# 09-I225-2.net
KiCad netlist of a schematic drawn in Altium Designer
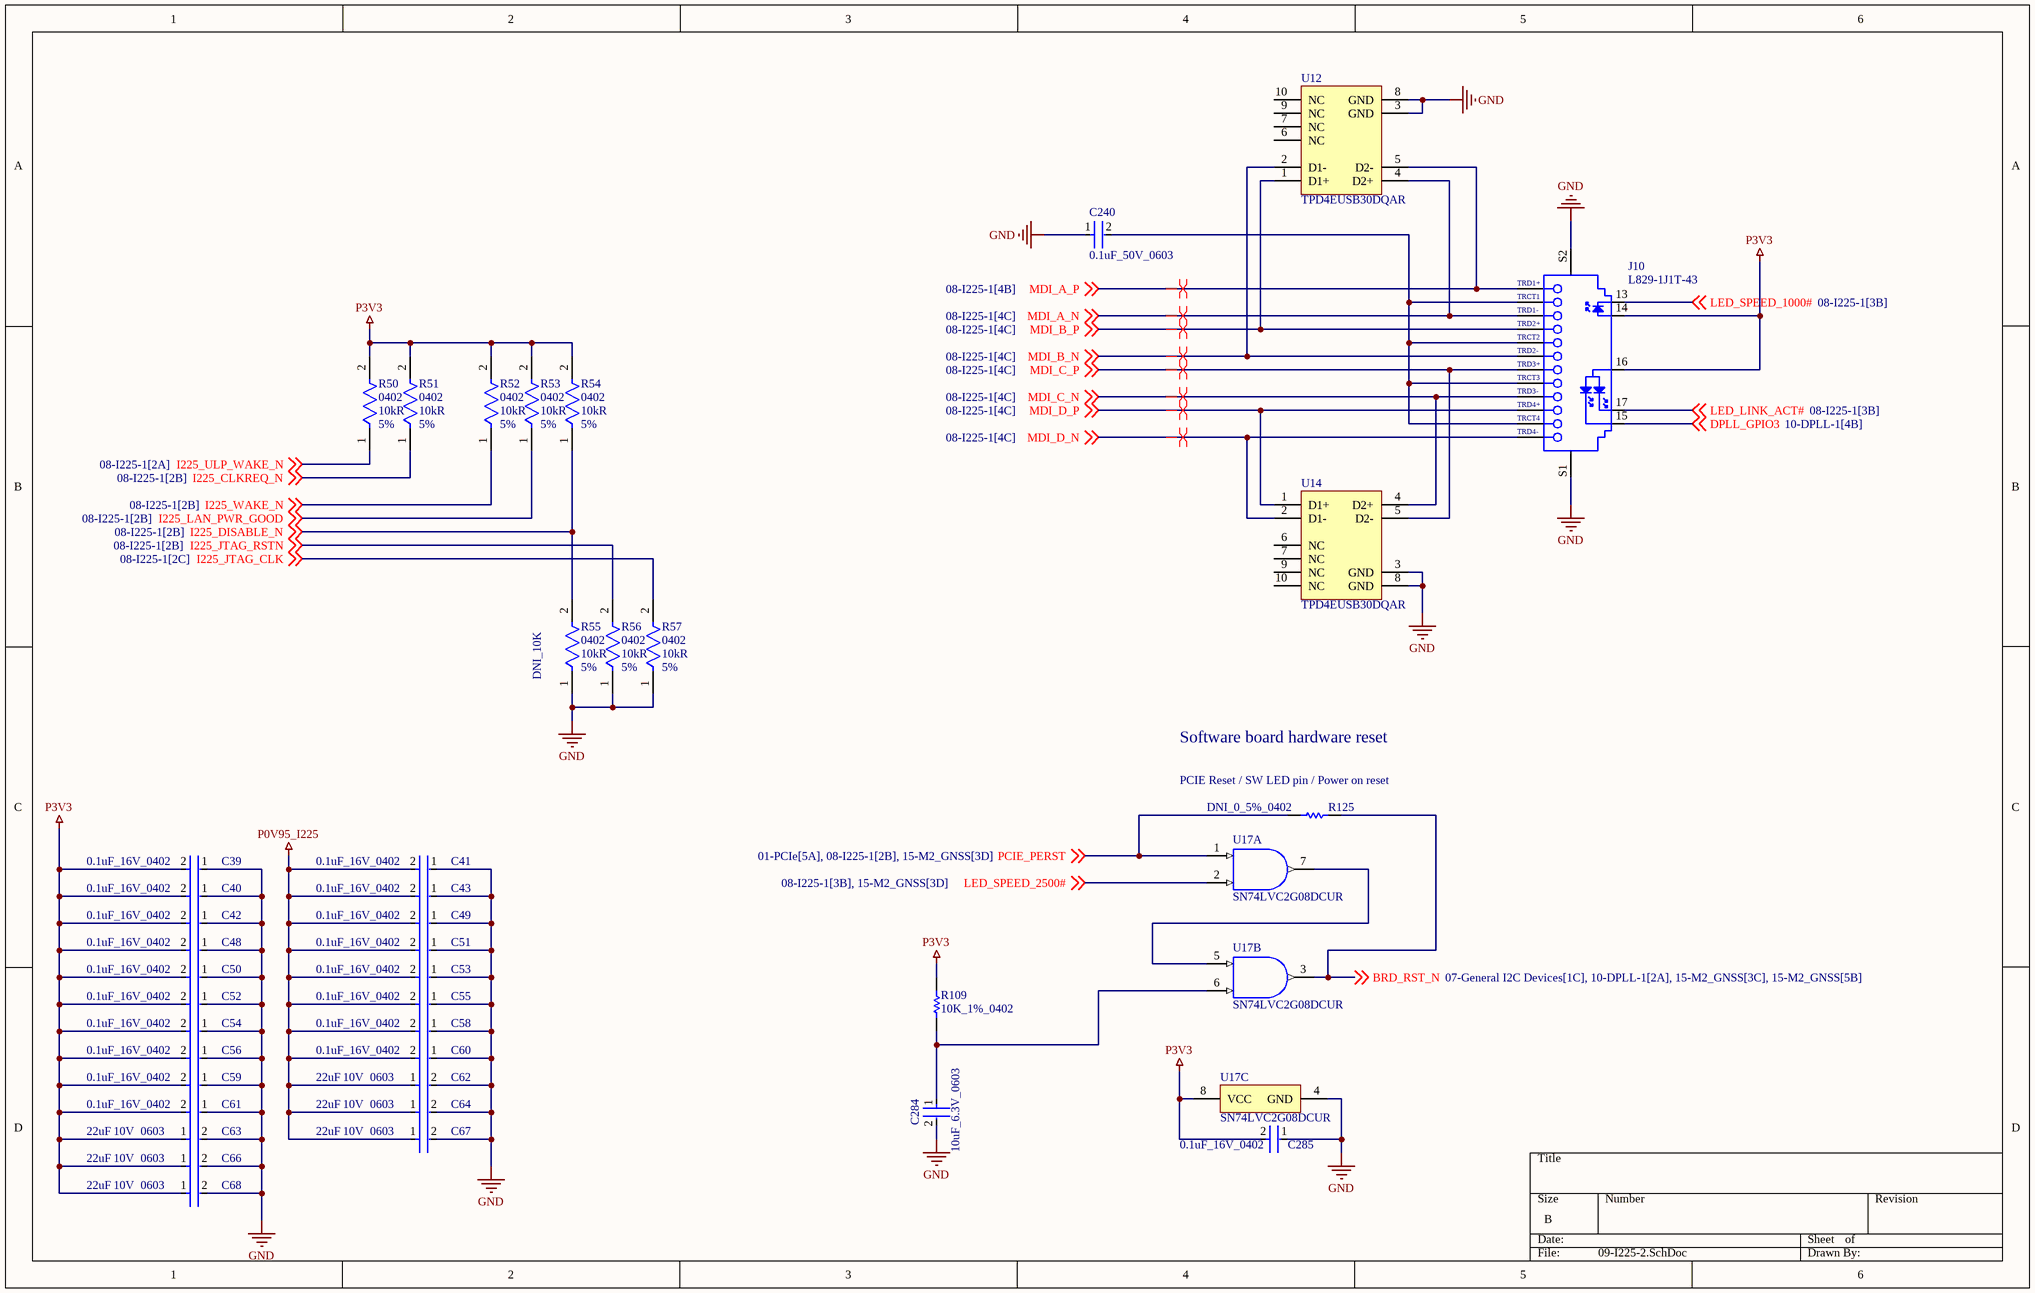
[diagram p0: 09-I225-2.SchDoc]

(export (version "E")
  (design (tool "Eeschema 10.0.6"))
  (components
    (comp (ref "C39")
      (value "0.1uF_16V_0402")
      (footprint "FP-GRM15-MFG")
      (description "CAP CER 0.1UF 16V X7R 0402")
      (fields (field (name "MANUFACTURER PART NUMBER") "GRM155R71C104KA88D") (field (name "TOLERANCE") "10%"))
      (libsource (lib "Altium Content Vault") (part "236180d848d6139a670b325ea6854c9"))
    )
    (comp (ref "C40")
      (value "0.1uF_16V_0402")
      (footprint "FP-GRM15-MFG")
      (description "CAP CER 0.1UF 16V X7R 0402")
      (fields (field (name "MANUFACTURER PART NUMBER") "GRM155R71C104KA88D") (field (name "TOLERANCE") "10%"))
      (libsource (lib "Altium Content Vault") (part "236180d848d6139a670b325ea6854c9"))
    )
    (comp (ref "C41")
      (value "0.1uF_16V_0402")
      (footprint "FP-GRM15-MFG")
      (description "CAP CER 0.1UF 16V X7R 0402")
      (fields (field (name "MANUFACTURER PART NUMBER") "GRM155R71C104KA88D") (field (name "TOLERANCE") "10%"))
      (libsource (lib "Altium Content Vault") (part "236180d848d6139a670b325ea6854c9"))
    )
    (comp (ref "C42")
      (value "0.1uF_16V_0402")
      (footprint "FP-GRM15-MFG")
      (description "CAP CER 0.1UF 16V X7R 0402")
      (fields (field (name "MANUFACTURER PART NUMBER") "GRM155R71C104KA88D") (field (name "TOLERANCE") "10%"))
      (libsource (lib "Altium Content Vault") (part "236180d848d6139a670b325ea6854c9"))
    )
    (comp (ref "C43")
      (value "0.1uF_16V_0402")
      (footprint "FP-GRM15-MFG")
      (description "CAP CER 0.1UF 16V X7R 0402")
      (fields (field (name "MANUFACTURER PART NUMBER") "GRM155R71C104KA88D") (field (name "TOLERANCE") "10%"))
      (libsource (lib "Altium Content Vault") (part "236180d848d6139a670b325ea6854c9"))
    )
    (comp (ref "C48")
      (value "0.1uF_16V_0402")
      (footprint "FP-GRM15-MFG")
      (description "CAP CER 0.1UF 16V X7R 0402")
      (fields (field (name "MANUFACTURER PART NUMBER") "GRM155R71C104KA88D") (field (name "TOLERANCE") "10%"))
      (libsource (lib "Altium Content Vault") (part "236180d848d6139a670b325ea6854c9"))
    )
    (comp (ref "C49")
      (value "0.1uF_16V_0402")
      (footprint "FP-GRM15-MFG")
      (description "CAP CER 0.1UF 16V X7R 0402")
      (fields (field (name "MANUFACTURER PART NUMBER") "GRM155R71C104KA88D") (field (name "TOLERANCE") "10%"))
      (libsource (lib "Altium Content Vault") (part "236180d848d6139a670b325ea6854c9"))
    )
    (comp (ref "C50")
      (value "0.1uF_16V_0402")
      (footprint "FP-GRM15-MFG")
      (description "CAP CER 0.1UF 16V X7R 0402")
      (fields (field (name "MANUFACTURER PART NUMBER") "GRM155R71C104KA88D") (field (name "TOLERANCE") "10%"))
      (libsource (lib "Altium Content Vault") (part "236180d848d6139a670b325ea6854c9"))
    )
    (comp (ref "C51")
      (value "0.1uF_16V_0402")
      (footprint "FP-GRM15-MFG")
      (description "CAP CER 0.1UF 16V X7R 0402")
      (fields (field (name "MANUFACTURER PART NUMBER") "GRM155R71C104KA88D") (field (name "TOLERANCE") "10%"))
      (libsource (lib "Altium Content Vault") (part "236180d848d6139a670b325ea6854c9"))
    )
    (comp (ref "C52")
      (value "0.1uF_16V_0402")
      (footprint "FP-GRM15-MFG")
      (description "CAP CER 0.1UF 16V X7R 0402")
      (fields (field (name "MANUFACTURER PART NUMBER") "GRM155R71C104KA88D") (field (name "TOLERANCE") "10%"))
      (libsource (lib "Altium Content Vault") (part "236180d848d6139a670b325ea6854c9"))
    )
    (comp (ref "C53")
      (value "0.1uF_16V_0402")
      (footprint "FP-GRM15-MFG")
      (description "CAP CER 0.1UF 16V X7R 0402")
      (fields (field (name "MANUFACTURER PART NUMBER") "GRM155R71C104KA88D") (field (name "TOLERANCE") "10%"))
      (libsource (lib "Altium Content Vault") (part "236180d848d6139a670b325ea6854c9"))
    )
    (comp (ref "C54")
      (value "0.1uF_16V_0402")
      (footprint "FP-GRM15-MFG")
      (description "CAP CER 0.1UF 16V X7R 0402")
      (fields (field (name "MANUFACTURER PART NUMBER") "GRM155R71C104KA88D") (field (name "TOLERANCE") "10%"))
      (libsource (lib "Altium Content Vault") (part "236180d848d6139a670b325ea6854c9"))
    )
    (comp (ref "C55")
      (value "0.1uF_16V_0402")
      (footprint "FP-GRM15-MFG")
      (description "CAP CER 0.1UF 16V X7R 0402")
      (fields (field (name "MANUFACTURER PART NUMBER") "GRM155R71C104KA88D") (field (name "TOLERANCE") "10%"))
      (libsource (lib "Altium Content Vault") (part "236180d848d6139a670b325ea6854c9"))
    )
    (comp (ref "C56")
      (value "0.1uF_16V_0402")
      (footprint "FP-GRM15-MFG")
      (description "CAP CER 0.1UF 16V X7R 0402")
      (fields (field (name "MANUFACTURER PART NUMBER") "GRM155R71C104KA88D") (field (name "TOLERANCE") "10%"))
      (libsource (lib "Altium Content Vault") (part "236180d848d6139a670b325ea6854c9"))
    )
    (comp (ref "C58")
      (value "0.1uF_16V_0402")
      (footprint "FP-GRM15-MFG")
      (description "CAP CER 0.1UF 16V X7R 0402")
      (fields (field (name "MANUFACTURER PART NUMBER") "GRM155R71C104KA88D") (field (name "TOLERANCE") "10%"))
      (libsource (lib "Altium Content Vault") (part "236180d848d6139a670b325ea6854c9"))
    )
    (comp (ref "C59")
      (value "0.1uF_16V_0402")
      (footprint "FP-GRM15-MFG")
      (description "CAP CER 0.1UF 16V X7R 0402")
      (fields (field (name "MANUFACTURER PART NUMBER") "GRM155R71C104KA88D") (field (name "TOLERANCE") "10%"))
      (libsource (lib "Altium Content Vault") (part "236180d848d6139a670b325ea6854c9"))
    )
    (comp (ref "C60")
      (value "0.1uF_16V_0402")
      (footprint "FP-GRM15-MFG")
      (description "CAP CER 0.1UF 16V X7R 0402")
      (fields (field (name "MANUFACTURER PART NUMBER") "GRM155R71C104KA88D") (field (name "TOLERANCE") "10%"))
      (libsource (lib "Altium Content Vault") (part "236180d848d6139a670b325ea6854c9"))
    )
    (comp (ref "C61")
      (value "0.1uF_16V_0402")
      (footprint "FP-GRM15-MFG")
      (description "CAP CER 0.1UF 16V X7R 0402")
      (fields (field (name "MANUFACTURER PART NUMBER") "GRM155R71C104KA88D") (field (name "TOLERANCE") "10%"))
      (libsource (lib "Altium Content Vault") (part "236180d848d6139a670b325ea6854c9"))
    )
    (comp (ref "C62")
      (value "GRM188R61A226ME15D")
      (footprint "FP-GRM188-0_2-IPC_C")
      (description "Chip Multilayer Ceramic Capacitors for General Purpose, 0603, 22uF, X5R, 15%, 20%, 10V")
      (fields
        (field (name "TOLERANCE") "20%")
        (field (name "CAPACITANCE") "22uF")
        (field (name "VOLTAGE RATING") "10V")
        (field (name "CASE CODE (IMPERIAL)") "0603")
      )
      (libsource (lib "Altium Content Vault") (part "11868f565c42a9108669ba33697ecf6"))
    )
    (comp (ref "C63")
      (value "GRM188R61A226ME15D")
      (footprint "FP-GRM188-0_2-IPC_C")
      (description "Chip Multilayer Ceramic Capacitors for General Purpose, 0603, 22uF, X5R, 15%, 20%, 10V")
      (fields
        (field (name "TOLERANCE") "20%")
        (field (name "CAPACITANCE") "22uF")
        (field (name "VOLTAGE RATING") "10V")
        (field (name "CASE CODE (IMPERIAL)") "0603")
      )
      (libsource (lib "Altium Content Vault") (part "11868f565c42a9108669ba33697ecf6"))
    )
    (comp (ref "C64")
      (value "GRM188R61A226ME15D")
      (footprint "FP-GRM188-0_2-IPC_C")
      (description "Chip Multilayer Ceramic Capacitors for General Purpose, 0603, 22uF, X5R, 15%, 20%, 10V")
      (fields
        (field (name "TOLERANCE") "20%")
        (field (name "CAPACITANCE") "22uF")
        (field (name "VOLTAGE RATING") "10V")
        (field (name "CASE CODE (IMPERIAL)") "0603")
      )
      (libsource (lib "Altium Content Vault") (part "11868f565c42a9108669ba33697ecf6"))
    )
    (comp (ref "C66")
      (value "GRM188R61A226ME15D")
      (footprint "FP-GRM188-0_2-IPC_C")
      (description "Chip Multilayer Ceramic Capacitors for General Purpose, 0603, 22uF, X5R, 15%, 20%, 10V")
      (fields
        (field (name "TOLERANCE") "20%")
        (field (name "CAPACITANCE") "22uF")
        (field (name "VOLTAGE RATING") "10V")
        (field (name "CASE CODE (IMPERIAL)") "0603")
      )
      (libsource (lib "Altium Content Vault") (part "11868f565c42a9108669ba33697ecf6"))
    )
    (comp (ref "C67")
      (value "GRM188R61A226ME15D")
      (footprint "FP-GRM188-0_2-IPC_C")
      (description "Chip Multilayer Ceramic Capacitors for General Purpose, 0603, 22uF, X5R, 15%, 20%, 10V")
      (fields
        (field (name "TOLERANCE") "20%")
        (field (name "CAPACITANCE") "22uF")
        (field (name "VOLTAGE RATING") "10V")
        (field (name "CASE CODE (IMPERIAL)") "0603")
      )
      (libsource (lib "Altium Content Vault") (part "11868f565c42a9108669ba33697ecf6"))
    )
    (comp (ref "C68")
      (value "GRM188R61A226ME15D")
      (footprint "FP-GRM188-0_2-IPC_C")
      (description "Chip Multilayer Ceramic Capacitors for General Purpose, 0603, 22uF, X5R, 15%, 20%, 10V")
      (fields
        (field (name "TOLERANCE") "20%")
        (field (name "CAPACITANCE") "22uF")
        (field (name "VOLTAGE RATING") "10V")
        (field (name "CASE CODE (IMPERIAL)") "0603")
      )
      (libsource (lib "Altium Content Vault") (part "11868f565c42a9108669ba33697ecf6"))
    )
    (comp (ref "C240")
      (value "0.1uF_50V_0603")
      (footprint "FP-C0603-CJ-MFG")
      (description "CAP CER 0.1UF 50V X7R 0603")
      (fields (field (name "MANUFACTURER PART NUMBER") "C0603X104K5RACTU") (field (name "VOLTAGE") "50V"))
      (libsource (lib "Altium Content Vault") (part "11868f565c42a9108669ba33697ecf6"))
    )
    (comp (ref "C284")
      (value "10uF_6.3V_0603")
      (footprint "FP-C0603C106M9PACTU-MFG")
      (description "CAP CER 10UF 6.3V X5R 0603")
      (fields
        (field (name "MANUFACTURER PART NUMBER") "C0603C106M9PACTU")
        (field (name "MANUFACTURER") "Kemet")
      )
      (libsource (lib "Altium Content Vault") (part "b4654b650e69147ec39a6b967a45e02"))
    )
    (comp (ref "C285")
      (value "0.1uF_16V_0402")
      (footprint "FP-GRM15-MFG")
      (description "CAP CER 0.1UF 16V X7R 0402")
      (fields (field (name "MANUFACTURER PART NUMBER") "GRM155R71C104KA88D") (field (name "TOLERANCE") "10%"))
      (libsource (lib "Altium Content Vault") (part "236180d848d6139a670b325ea6854c9"))
    )
    (comp (ref "J10")
      (value "L829-1J1T-43")
      (footprint "BELS-L829-1J1T-43_V")
      (description "Gigabit MagJack(R) Ultra Low Profile, 10/100/1000 Base-T, 19-Pin THD, RoHS, Tray")
      (libsource (lib "Altium Content Vault") (part "RJ45-17-2SHLD"))
    )
    (comp (ref "R50")
      (value "CRCW040210K0JNED")
      (footprint "FP-CRCW0402-e3-IPC_B")
      (description "RES Thick Film, 10kΩ, 5%, 0.063W, 200ppm/°C, 0402")
      (fields
        (field (name "CASE/PACKAGE") "0402")
        (field (name "RESISTANCE") "10kR")
        (field (name "TOLERANCE") "5%")
      )
      (libsource (lib "Altium Content Vault") (part "1029c3af85768c4190bb7ad29bc67b5"))
    )
    (comp (ref "R51")
      (value "CRCW040210K0JNED")
      (footprint "FP-CRCW0402-e3-IPC_B")
      (description "RES Thick Film, 10kΩ, 5%, 0.063W, 200ppm/°C, 0402")
      (fields
        (field (name "CASE/PACKAGE") "0402")
        (field (name "RESISTANCE") "10kR")
        (field (name "TOLERANCE") "5%")
      )
      (libsource (lib "Altium Content Vault") (part "1029c3af85768c4190bb7ad29bc67b5"))
    )
    (comp (ref "R52")
      (value "CRCW040210K0JNED")
      (footprint "FP-CRCW0402-e3-IPC_B")
      (description "RES Thick Film, 10kΩ, 5%, 0.063W, 200ppm/°C, 0402")
      (fields
        (field (name "CASE/PACKAGE") "0402")
        (field (name "RESISTANCE") "10kR")
        (field (name "TOLERANCE") "5%")
      )
      (libsource (lib "Altium Content Vault") (part "1029c3af85768c4190bb7ad29bc67b5"))
    )
    (comp (ref "R53")
      (value "CRCW040210K0JNED")
      (footprint "FP-CRCW0402-e3-IPC_B")
      (description "RES Thick Film, 10kΩ, 5%, 0.063W, 200ppm/°C, 0402")
      (fields
        (field (name "CASE/PACKAGE") "0402")
        (field (name "RESISTANCE") "10kR")
        (field (name "TOLERANCE") "5%")
      )
      (libsource (lib "Altium Content Vault") (part "1029c3af85768c4190bb7ad29bc67b5"))
    )
    (comp (ref "R54")
      (value "CRCW040210K0JNED")
      (footprint "FP-CRCW0402-e3-IPC_B")
      (description "RES Thick Film, 10kΩ, 5%, 0.063W, 200ppm/°C, 0402")
      (fields
        (field (name "CASE/PACKAGE") "0402")
        (field (name "RESISTANCE") "10kR")
        (field (name "TOLERANCE") "5%")
      )
      (libsource (lib "Altium Content Vault") (part "1029c3af85768c4190bb7ad29bc67b5"))
    )
    (comp (ref "R55")
      (value "DNI_10K")
      (footprint "FP-CRCW0402-e3-IPC_B")
      (description "RES Thick Film, 10kΩ, 5%, 0.063W, 200ppm/°C, 0402")
      (fields
        (field (name "CASE/PACKAGE") "0402")
        (field (name "RESISTANCE") "10kR")
        (field (name "TOLERANCE") "5%")
      )
      (libsource (lib "Altium Content Vault") (part "1029c3af85768c4190bb7ad29bc67b5"))
    )
    (comp (ref "R56")
      (value "CRCW040210K0JNED")
      (footprint "FP-CRCW0402-e3-IPC_B")
      (description "RES Thick Film, 10kΩ, 5%, 0.063W, 200ppm/°C, 0402")
      (fields
        (field (name "CASE/PACKAGE") "0402")
        (field (name "RESISTANCE") "10kR")
        (field (name "TOLERANCE") "5%")
      )
      (libsource (lib "Altium Content Vault") (part "1029c3af85768c4190bb7ad29bc67b5"))
    )
    (comp (ref "R57")
      (value "CRCW040210K0JNED")
      (footprint "FP-CRCW0402-e3-IPC_B")
      (description "RES Thick Film, 10kΩ, 5%, 0.063W, 200ppm/°C, 0402")
      (fields
        (field (name "CASE/PACKAGE") "0402")
        (field (name "RESISTANCE") "10kR")
        (field (name "TOLERANCE") "5%")
      )
      (libsource (lib "Altium Content Vault") (part "1029c3af85768c4190bb7ad29bc67b5"))
    )
    (comp (ref "R109")
      (value "10K_1%_0402")
      (footprint "RESC1005X40X25NL10T10")
      (fields (field (name "MANUFACTURER") "Bourns") (field (name "PART NUMBER") "CR0402-FX-1002GLF"))
      (libsource (lib "Altium Content Vault") (part "RES"))
    )
    (comp (ref "R125")
      (value "DNI_0_5%_0402")
      (footprint "RESC1005X40X25LL10T10")
      (fields (field (name "MANUFACTURER") "KOA Speer") (field (name "PART NUMBER") "RK73Z1ETTP"))
      (libsource (lib "Altium Content Vault") (part "RES"))
    )
    (comp (ref "U12")
      (value "TPD4EUSB30DQAR")
      (footprint "DQA0010A_V")
      (fields (field (name "MANUFACTURER") "Texas Instruments"))
      (libsource (lib "Altium Content Vault") (part "TI-TPD4EUSB30-SON_DQA-10"))
    )
    (comp (ref "U14")
      (value "TPD4EUSB30DQAR")
      (footprint "DQA0010A_V")
      (fields (field (name "MANUFACTURER") "Texas Instruments"))
      (libsource (lib "") (part "TI-TPD4EUSB30-SON_DQA-10_1"))
    )
    (comp (ref "U17")
      (value "SN74LVC2G08DCUR")
      (footprint "DCU0008A_M")
      (description "Dual 2-Input Positive-AND Gate, DCU0008A, LARGE T&R")
      (fields
        (field (name "MANUFACTURER") "Texas Instruments")
        (field (name "GENERIC PART NUMBER") "SN74LVC2G08")
      )
      (libsource (lib "Altium Content Vault") (part "TI-SN74XXX2G08-8"))
    )
  )
  (nets
    (net (code "1") (name "BRD_RST_N") (class "Default")
      (node (ref "R125") (pin "2") (pinfunction "2_2") (pintype "passive"))
      (node (ref "U17") (pin "3") (pinfunction "2Y_3") (pintype "output"))
    )
    (net (code "2") (name "DPLL_GPIO3") (class "Default")
      (node (ref "J10") (pin "15") (pinfunction "15_15") (pintype "passive"))
    )
    (net (code "3") (name "GND") (class "Default")
      (node (ref "C240") (pin "1") (pinfunction "1_1") (pintype "passive"))
      (node (ref "C284") (pin "2") (pinfunction "2_2") (pintype "passive"))
      (node (ref "C285") (pin "1") (pinfunction "1_1") (pintype "passive"))
      (node (ref "C39") (pin "1") (pinfunction "1_1") (pintype "passive"))
      (node (ref "C40") (pin "1") (pinfunction "1_1") (pintype "passive"))
      (node (ref "C41") (pin "1") (pinfunction "1_1") (pintype "passive"))
      (node (ref "C42") (pin "1") (pinfunction "1_1") (pintype "passive"))
      (node (ref "C43") (pin "1") (pinfunction "1_1") (pintype "passive"))
      (node (ref "C48") (pin "1") (pinfunction "1_1") (pintype "passive"))
      (node (ref "C49") (pin "1") (pinfunction "1_1") (pintype "passive"))
      (node (ref "C50") (pin "1") (pinfunction "1_1") (pintype "passive"))
      (node (ref "C51") (pin "1") (pinfunction "1_1") (pintype "passive"))
      (node (ref "C52") (pin "1") (pinfunction "1_1") (pintype "passive"))
      (node (ref "C53") (pin "1") (pinfunction "1_1") (pintype "passive"))
      (node (ref "C54") (pin "1") (pinfunction "1_1") (pintype "passive"))
      (node (ref "C55") (pin "1") (pinfunction "1_1") (pintype "passive"))
      (node (ref "C56") (pin "1") (pinfunction "1_1") (pintype "passive"))
      (node (ref "C58") (pin "1") (pinfunction "1_1") (pintype "passive"))
      (node (ref "C59") (pin "1") (pinfunction "1_1") (pintype "passive"))
      (node (ref "C60") (pin "1") (pinfunction "1_1") (pintype "passive"))
      (node (ref "C61") (pin "1") (pinfunction "1_1") (pintype "passive"))
      (node (ref "C62") (pin "2") (pinfunction "2_2") (pintype "passive"))
      (node (ref "C63") (pin "2") (pinfunction "2_2") (pintype "passive"))
      (node (ref "C64") (pin "2") (pinfunction "2_2") (pintype "passive"))
      (node (ref "C66") (pin "2") (pinfunction "2_2") (pintype "passive"))
      (node (ref "C67") (pin "2") (pinfunction "2_2") (pintype "passive"))
      (node (ref "C68") (pin "2") (pinfunction "2_2") (pintype "passive"))
      (node (ref "J10") (pin "S1") (pinfunction "S1_S1") (pintype "passive"))
      (node (ref "J10") (pin "S2") (pinfunction "S2_S2") (pintype "passive"))
      (node (ref "R55") (pin "1") (pinfunction "1_1") (pintype "passive"))
      (node (ref "R56") (pin "1") (pinfunction "1_1") (pintype "passive"))
      (node (ref "R57") (pin "1") (pinfunction "1_1") (pintype "passive"))
      (node (ref "U12") (pin "3") (pinfunction "GND_3") (pintype "power_in"))
      (node (ref "U12") (pin "8") (pinfunction "GND_8") (pintype "power_in"))
      (node (ref "U14") (pin "3") (pinfunction "GND_3") (pintype "power_in"))
      (node (ref "U14") (pin "8") (pinfunction "GND_8") (pintype "power_in"))
      (node (ref "U17") (pin "4") (pinfunction "GND_4") (pintype "power_in"))
    )
    (net (code "4") (name "I225_CLKREQ_N") (class "Default")
      (node (ref "R51") (pin "1") (pinfunction "1_1") (pintype "passive"))
    )
    (net (code "5") (name "I225_DISABLE_N") (class "Default")
      (node (ref "R54") (pin "1") (pinfunction "1_1") (pintype "passive"))
      (node (ref "R55") (pin "2") (pinfunction "2_2") (pintype "passive"))
    )
    (net (code "6") (name "I225_JTAG_CLK") (class "Default")
      (node (ref "R57") (pin "2") (pinfunction "2_2") (pintype "passive"))
    )
    (net (code "7") (name "I225_JTAG_RSTN") (class "Default")
      (node (ref "R56") (pin "2") (pinfunction "2_2") (pintype "passive"))
    )
    (net (code "8") (name "I225_LAN_PWR_GOOD") (class "Default")
      (node (ref "R53") (pin "1") (pinfunction "1_1") (pintype "passive"))
    )
    (net (code "9") (name "I225_ULP_WAKE_N") (class "Default")
      (node (ref "R50") (pin "1") (pinfunction "1_1") (pintype "passive"))
    )
    (net (code "10") (name "I225_WAKE_N") (class "Default")
      (node (ref "R52") (pin "1") (pinfunction "1_1") (pintype "passive"))
    )
    (net (code "11") (name "LED_LINK_ACT#") (class "Default")
      (node (ref "J10") (pin "17") (pinfunction "17_17") (pintype "passive"))
    )
    (net (code "12") (name "LED_SPEED_1000#") (class "Default")
      (node (ref "J10") (pin "13") (pinfunction "13_13") (pintype "passive"))
    )
    (net (code "13") (name "LED_SPEED_2500#") (class "Default")
      (node (ref "U17") (pin "2") (pinfunction "1B_2") (pintype "input"))
    )
    (net (code "14") (name "MDI_A_N") (class "Default")
      (node (ref "J10") (pin "3") (pinfunction "TRD1-_3") (pintype "passive"))
      (node (ref "U12") (pin "4") (pinfunction "D2+_4") (pintype "passive"))
    )
    (net (code "15") (name "MDI_A_P") (class "Default")
      (node (ref "J10") (pin "1") (pinfunction "TRD1+_1") (pintype "passive"))
      (node (ref "U12") (pin "5") (pinfunction "D2-_5") (pintype "passive"))
    )
    (net (code "16") (name "MDI_B_N") (class "Default")
      (node (ref "J10") (pin "6") (pinfunction "TRD2-_6") (pintype "passive"))
      (node (ref "U12") (pin "2") (pinfunction "D1-_2") (pintype "passive"))
    )
    (net (code "17") (name "MDI_B_P") (class "Default")
      (node (ref "J10") (pin "4") (pinfunction "TRD2+_4") (pintype "passive"))
      (node (ref "U12") (pin "1") (pinfunction "D1+_1") (pintype "passive"))
    )
    (net (code "18") (name "MDI_C_N") (class "Default")
      (node (ref "J10") (pin "9") (pinfunction "TRD3-_9") (pintype "passive"))
      (node (ref "U14") (pin "4") (pinfunction "D2+_4") (pintype "passive"))
    )
    (net (code "19") (name "MDI_C_P") (class "Default")
      (node (ref "J10") (pin "7") (pinfunction "TRD3+_7") (pintype "passive"))
      (node (ref "U14") (pin "5") (pinfunction "D2-_5") (pintype "passive"))
    )
    (net (code "20") (name "MDI_D_N") (class "Default")
      (node (ref "J10") (pin "12") (pinfunction "TRD4-_12") (pintype "passive"))
      (node (ref "U14") (pin "2") (pinfunction "D1-_2") (pintype "passive"))
    )
    (net (code "21") (name "MDI_D_P") (class "Default")
      (node (ref "J10") (pin "10") (pinfunction "TRD4+_10") (pintype "passive"))
      (node (ref "U14") (pin "1") (pinfunction "D1+_1") (pintype "passive"))
    )
    (net (code "22") (name "Net-(J10-TRCT1)") (class "Default")
      (node (ref "C240") (pin "2") (pinfunction "2_2") (pintype "passive"))
      (node (ref "J10") (pin "11") (pinfunction "TRCT4_11") (pintype "passive"))
      (node (ref "J10") (pin "2") (pinfunction "TRCT1_2") (pintype "passive"))
      (node (ref "J10") (pin "5") (pinfunction "TRCT2_5") (pintype "passive"))
      (node (ref "J10") (pin "8") (pinfunction "TRCT3_8") (pintype "passive"))
    )
    (net (code "23") (name "Net-(U17A-1Y)") (class "Default")
      (node (ref "U17") (pin "5") (pinfunction "2A_5") (pintype "input"))
      (node (ref "U17") (pin "7") (pinfunction "1Y_7") (pintype "output"))
    )
    (net (code "24") (name "Net-(U17B-2B)") (class "Default")
      (node (ref "C284") (pin "1") (pinfunction "1_1") (pintype "passive"))
      (node (ref "R109") (pin "1") (pinfunction "1_1") (pintype "passive"))
      (node (ref "U17") (pin "6") (pinfunction "2B_6") (pintype "input"))
    )
    (net (code "25") (name "P0V95_I225") (class "Default")
      (node (ref "C41") (pin "2") (pinfunction "2_2") (pintype "passive"))
      (node (ref "C43") (pin "2") (pinfunction "2_2") (pintype "passive"))
      (node (ref "C49") (pin "2") (pinfunction "2_2") (pintype "passive"))
      (node (ref "C51") (pin "2") (pinfunction "2_2") (pintype "passive"))
      (node (ref "C53") (pin "2") (pinfunction "2_2") (pintype "passive"))
      (node (ref "C55") (pin "2") (pinfunction "2_2") (pintype "passive"))
      (node (ref "C58") (pin "2") (pinfunction "2_2") (pintype "passive"))
      (node (ref "C60") (pin "2") (pinfunction "2_2") (pintype "passive"))
      (node (ref "C62") (pin "1") (pinfunction "1_1") (pintype "passive"))
      (node (ref "C64") (pin "1") (pinfunction "1_1") (pintype "passive"))
      (node (ref "C67") (pin "1") (pinfunction "1_1") (pintype "passive"))
    )
    (net (code "26") (name "P3V3") (class "Default")
      (node (ref "C285") (pin "2") (pinfunction "2_2") (pintype "passive"))
      (node (ref "C39") (pin "2") (pinfunction "2_2") (pintype "passive"))
      (node (ref "C40") (pin "2") (pinfunction "2_2") (pintype "passive"))
      (node (ref "C42") (pin "2") (pinfunction "2_2") (pintype "passive"))
      (node (ref "C48") (pin "2") (pinfunction "2_2") (pintype "passive"))
      (node (ref "C50") (pin "2") (pinfunction "2_2") (pintype "passive"))
      (node (ref "C52") (pin "2") (pinfunction "2_2") (pintype "passive"))
      (node (ref "C54") (pin "2") (pinfunction "2_2") (pintype "passive"))
      (node (ref "C56") (pin "2") (pinfunction "2_2") (pintype "passive"))
      (node (ref "C59") (pin "2") (pinfunction "2_2") (pintype "passive"))
      (node (ref "C61") (pin "2") (pinfunction "2_2") (pintype "passive"))
      (node (ref "C63") (pin "1") (pinfunction "1_1") (pintype "passive"))
      (node (ref "C66") (pin "1") (pinfunction "1_1") (pintype "passive"))
      (node (ref "C68") (pin "1") (pinfunction "1_1") (pintype "passive"))
      (node (ref "J10") (pin "14") (pinfunction "14_14") (pintype "passive"))
      (node (ref "J10") (pin "16") (pinfunction "16_16") (pintype "passive"))
      (node (ref "R109") (pin "2") (pinfunction "2_2") (pintype "passive"))
      (node (ref "R50") (pin "2") (pinfunction "2_2") (pintype "passive"))
      (node (ref "R51") (pin "2") (pinfunction "2_2") (pintype "passive"))
      (node (ref "R52") (pin "2") (pinfunction "2_2") (pintype "passive"))
      (node (ref "R53") (pin "2") (pinfunction "2_2") (pintype "passive"))
      (node (ref "R54") (pin "2") (pinfunction "2_2") (pintype "passive"))
      (node (ref "U17") (pin "8") (pinfunction "VCC_8") (pintype "power_in"))
    )
    (net (code "27") (name "PCIE_PERST") (class "Default")
      (node (ref "R125") (pin "1") (pinfunction "1_1") (pintype "passive"))
      (node (ref "U17") (pin "1") (pinfunction "1A_1") (pintype "input"))
    )
    (net (code "28") (name "unconnected-(U12-NC-Pad6)") (class "Default")
      (node (ref "U12") (pin "6") (pinfunction "NC_6") (pintype "passive"))
    )
    (net (code "29") (name "unconnected-(U12-NC-Pad7)") (class "Default")
      (node (ref "U12") (pin "7") (pinfunction "NC_7") (pintype "passive"))
    )
    (net (code "30") (name "unconnected-(U12-NC-Pad9)") (class "Default")
      (node (ref "U12") (pin "9") (pinfunction "NC_9") (pintype "passive"))
    )
    (net (code "31") (name "unconnected-(U12-NC-Pad10)") (class "Default")
      (node (ref "U12") (pin "10") (pinfunction "NC_10") (pintype "passive"))
    )
    (net (code "32") (name "unconnected-(U14-NC-Pad6)") (class "Default")
      (node (ref "U14") (pin "6") (pinfunction "NC_6") (pintype "passive"))
    )
    (net (code "33") (name "unconnected-(U14-NC-Pad7)") (class "Default")
      (node (ref "U14") (pin "7") (pinfunction "NC_7") (pintype "passive"))
    )
    (net (code "34") (name "unconnected-(U14-NC-Pad9)") (class "Default")
      (node (ref "U14") (pin "9") (pinfunction "NC_9") (pintype "passive"))
    )
    (net (code "35") (name "unconnected-(U14-NC-Pad10)") (class "Default")
      (node (ref "U14") (pin "10") (pinfunction "NC_10") (pintype "passive"))
    )
  )
)
